# FDTI2DMX.net
KiCad netlist of a schematic drawn in EAGLE
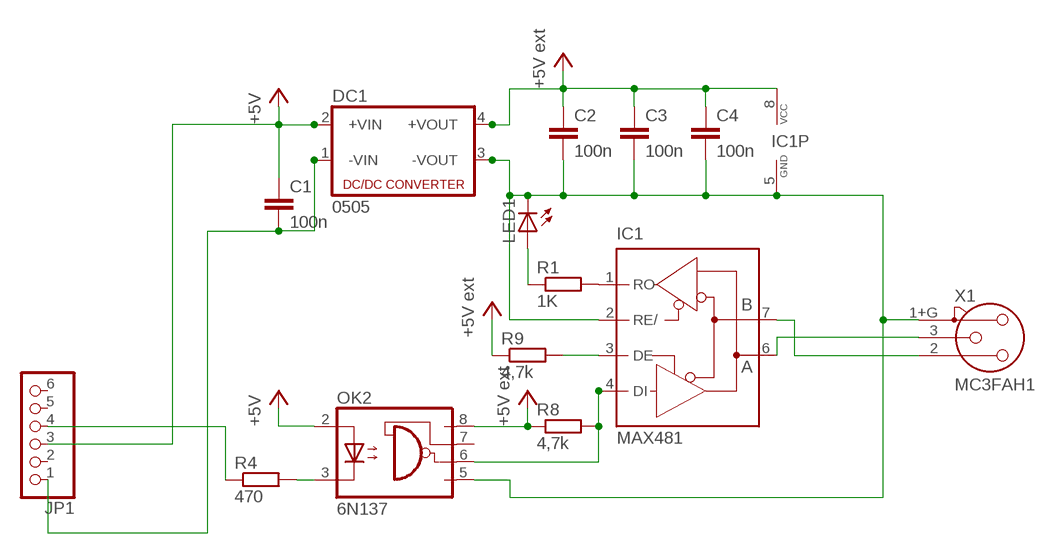
[diagram p0: schematic, sheet 1]

(export (version "E")
  (design (tool "Eeschema 10.0.6"))
  (components
    (comp (ref "C1")
      (value "100n")
      (footprint "eagle-import:C5B3")
      (libsource (lib "eagle-import") (part "C5/3"))
    )
    (comp (ref "C2")
      (value "100n")
      (footprint "eagle-import:C7.5B3")
      (libsource (lib "eagle-import") (part "C7.5/3"))
    )
    (comp (ref "C3")
      (value "100n")
      (footprint "eagle-import:C7.5B3")
      (libsource (lib "eagle-import") (part "C7.5/3"))
    )
    (comp (ref "C4")
      (value "100n")
      (footprint "eagle-import:C7.5B3")
      (libsource (lib "eagle-import") (part "C7.5/3"))
    )
    (comp (ref "DC1")
      (value "0505")
      (footprint "eagle-import:NME")
      (fields (field (name "MF") "C & D TECHNOLOGIES, INC") (field (name "MPN") "NME1205D"))
      (libsource (lib "eagle-import") (part "NME"))
    )
    (comp (ref "IC1")
      (value "MAX481")
      (footprint "eagle-import:DIL08")
      (fields (field (name "MPN") "MAX481CPA+"))
      (libsource (lib "eagle-import") (part "MAX481CPA"))
    )
    (comp (ref "JP1")
      (value "PINHD-1X6/90")
      (footprint "eagle-import:1X06_90")
      (libsource (lib "eagle-import") (part "PINHD-1X6/90"))
    )
    (comp (ref "LED1")
      (value "LED3MM")
      (footprint "eagle-import:LED3MM")
      (libsource (lib "eagle-import") (part "LED3MM"))
    )
    (comp (ref "OK2")
      (value "6N137")
      (footprint "eagle-import:DIL08")
      (libsource (lib "eagle-import") (part "6N137"))
    )
    (comp (ref "R1")
      (value "1K")
      (footprint "eagle-import:0207_10")
      (libsource (lib "eagle-import") (part "R-EU_0207/10"))
    )
    (comp (ref "R4")
      (value "470")
      (footprint "eagle-import:0207_10")
      (libsource (lib "eagle-import") (part "R-EU_0207/10"))
    )
    (comp (ref "R8")
      (value "4,7k")
      (footprint "eagle-import:0204_7")
      (libsource (lib "eagle-import") (part "R-EU_0204/7"))
    )
    (comp (ref "R9")
      (value "4,7k")
      (footprint "eagle-import:0204_7")
      (libsource (lib "eagle-import") (part "R-EU_0204/7"))
    )
    (comp (ref "X1")
      (value "MC3FAH1")
      (footprint "eagle-import:NC3FAH1")
      (libsource (lib "eagle-import") (part "MC3?FAH1"))
    )
  )
  (nets
    (net (code "1") (name "+5V") (class "Default")
      (node (ref "C1") (pin "1") (pinfunction "1_1") (pintype "passive"))
      (node (ref "DC1") (pin "2") (pinfunction "+VIN_2") (pintype "passive"))
      (node (ref "JP1") (pin "3") (pinfunction "3_3") (pintype "passive"))
      (node (ref "OK2") (pin "2") (pinfunction "A_2") (pintype "passive"))
    )
    (net (code "2") (name "+5V ext") (class "Default")
      (node (ref "C2") (pin "1") (pinfunction "1_1") (pintype "passive"))
      (node (ref "C3") (pin "1") (pinfunction "1_1") (pintype "passive"))
      (node (ref "C4") (pin "1") (pinfunction "1_1") (pintype "passive"))
      (node (ref "DC1") (pin "4") (pinfunction "+VOUT_4") (pintype "passive"))
      (node (ref "IC1") (pin "8") (pinfunction "VCC_8") (pintype "power_in"))
      (node (ref "OK2") (pin "8") (pinfunction "VCC_8") (pintype "passive"))
      (node (ref "R8") (pin "1") (pinfunction "1_1") (pintype "passive"))
      (node (ref "R9") (pin "1") (pinfunction "1_1") (pintype "passive"))
    )
    (net (code "3") (name "Net-(DC1--VIN)") (class "Default")
      (node (ref "C1") (pin "2") (pinfunction "2_2") (pintype "passive"))
      (node (ref "DC1") (pin "1") (pinfunction "-VIN_1") (pintype "passive"))
      (node (ref "JP1") (pin "1") (pinfunction "1_1") (pintype "passive"))
    )
    (net (code "4") (name "Net-(DC1--VOUT)") (class "Default")
      (node (ref "C2") (pin "2") (pinfunction "2_2") (pintype "passive"))
      (node (ref "C3") (pin "2") (pinfunction "2_2") (pintype "passive"))
      (node (ref "C4") (pin "2") (pinfunction "2_2") (pintype "passive"))
      (node (ref "DC1") (pin "3") (pinfunction "-VOUT_3") (pintype "passive"))
      (node (ref "IC1") (pin "2") (pinfunction "RE/_2") (pintype "input"))
      (node (ref "IC1") (pin "5") (pinfunction "GND_5") (pintype "power_in"))
      (node (ref "LED1") (pin "K") (pinfunction "C_K") (pintype "passive"))
      (node (ref "OK2") (pin "5") (pinfunction "GND_5") (pintype "passive"))
      (node (ref "X1") (pin "1+G") (pinfunction "1_1+G") (pintype "passive"))
    )
    (net (code "5") (name "Net-(IC1A-A)") (class "Default")
      (node (ref "IC1") (pin "6") (pinfunction "A_6") (pintype "passive"))
      (node (ref "X1") (pin "3") (pinfunction "3_3") (pintype "passive"))
    )
    (net (code "6") (name "Net-(IC1A-B)") (class "Default")
      (node (ref "IC1") (pin "7") (pinfunction "B_7") (pintype "passive"))
      (node (ref "X1") (pin "2") (pinfunction "2_2") (pintype "passive"))
    )
    (net (code "7") (name "Net-(IC1A-DE)") (class "Default")
      (node (ref "IC1") (pin "3") (pinfunction "DE_3") (pintype "input"))
      (node (ref "R9") (pin "2") (pinfunction "2_2") (pintype "passive"))
    )
    (net (code "8") (name "Net-(IC1A-DI)") (class "Default")
      (node (ref "IC1") (pin "4") (pinfunction "DI_4") (pintype "input"))
      (node (ref "OK2") (pin "6") (pinfunction "VO_6") (pintype "passive"))
      (node (ref "R8") (pin "2") (pinfunction "2_2") (pintype "passive"))
    )
    (net (code "9") (name "Net-(IC1A-RO)") (class "Default")
      (node (ref "IC1") (pin "1") (pinfunction "RO_1") (pintype "output"))
      (node (ref "R1") (pin "2") (pinfunction "2_2") (pintype "passive"))
    )
    (net (code "10") (name "Net-(JP1-Pad4)") (class "Default")
      (node (ref "JP1") (pin "4") (pinfunction "4_4") (pintype "passive"))
      (node (ref "R4") (pin "1") (pinfunction "1_1") (pintype "passive"))
    )
    (net (code "11") (name "Net-(LED1-PadA)") (class "Default")
      (node (ref "LED1") (pin "A") (pinfunction "A_A") (pintype "passive"))
      (node (ref "R1") (pin "1") (pinfunction "1_1") (pintype "passive"))
    )
    (net (code "12") (name "Net-(OK2-C)") (class "Default")
      (node (ref "OK2") (pin "3") (pinfunction "C_3") (pintype "passive"))
      (node (ref "R4") (pin "2") (pinfunction "2_2") (pintype "passive"))
    )
    (net (code "13") (name "unconnected-(JP1-Pad2)") (class "Default")
      (node (ref "JP1") (pin "2") (pinfunction "2_2") (pintype "passive"))
    )
    (net (code "14") (name "unconnected-(JP1-Pad5)") (class "Default")
      (node (ref "JP1") (pin "5") (pinfunction "5_5") (pintype "passive"))
    )
    (net (code "15") (name "unconnected-(JP1-Pad6)") (class "Default")
      (node (ref "JP1") (pin "6") (pinfunction "6_6") (pintype "passive"))
    )
    (net (code "16") (name "unconnected-(OK2-VE-Pad7)") (class "Default")
      (node (ref "OK2") (pin "7") (pinfunction "VE_7") (pintype "passive"))
    )
  )
)
